# Beaglebone.net
KiCad netlist of a schematic drawn in Altium Designer
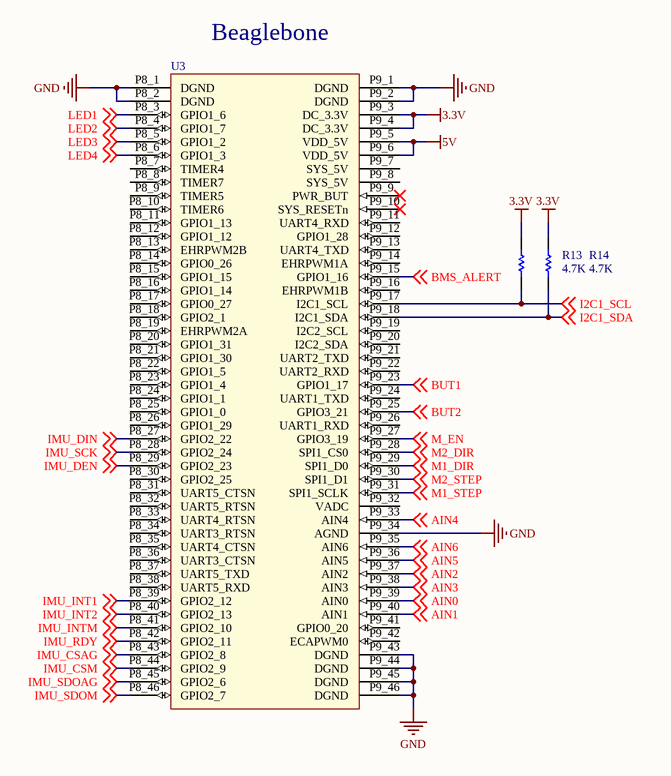
[diagram p0: Beaglebone.SchDoc]

(export (version "E")
  (design (tool "Eeschema 10.0.6"))
  (components
    (comp (ref "R13")
      (value "4.7K")
      (footprint "J1-0603")
      (description "RES SMD 4.7K OHM 5% 1/10W 0603")
      (libsource (lib "Miscellaneous Devices") (part "Res1"))
    )
    (comp (ref "R14")
      (value "4.7K")
      (footprint "J1-0603")
      (description "RES SMD 4.7K OHM 5% 1/10W 0603")
      (libsource (lib "Miscellaneous Devices") (part "Res1"))
    )
    (comp (ref "U3")
      (value "Beaglebone Black")
      (footprint "BEAGLEBONE_BLACK")
      (libsource (lib "MicromouseLib") (part "Beaglebone Black"))
    )
  )
  (nets
    (net (code "1") (name "3.3V") (class "Default")
      (node (ref "R13") (pin "2") (pinfunction "2_2") (pintype "passive"))
      (node (ref "R14") (pin "2") (pinfunction "2_2") (pintype "passive"))
      (node (ref "U3") (pin "P9_3") (pinfunction "DC_3.3V_P9_3") (pintype "power_in"))
      (node (ref "U3") (pin "P9_4") (pinfunction "DC_3.3V_P9_4") (pintype "power_in"))
    )
    (net (code "2") (name "5V") (class "Default")
      (node (ref "U3") (pin "P9_5") (pinfunction "VDD_5V_P9_5") (pintype "power_in"))
      (node (ref "U3") (pin "P9_6") (pinfunction "VDD_5V_P9_6") (pintype "power_in"))
    )
    (net (code "3") (name "AIN0") (class "Default")
      (node (ref "U3") (pin "P9_39") (pinfunction "AIN0_P9_39") (pintype "input"))
    )
    (net (code "4") (name "AIN1") (class "Default")
      (node (ref "U3") (pin "P9_40") (pinfunction "AIN1_P9_40") (pintype "input"))
    )
    (net (code "5") (name "AIN2") (class "Default")
      (node (ref "U3") (pin "P9_37") (pinfunction "AIN2_P9_37") (pintype "input"))
    )
    (net (code "6") (name "AIN3") (class "Default")
      (node (ref "U3") (pin "P9_38") (pinfunction "AIN3_P9_38") (pintype "input"))
    )
    (net (code "7") (name "AIN4") (class "Default")
      (node (ref "U3") (pin "P9_33") (pinfunction "AIN4_P9_33") (pintype "input"))
    )
    (net (code "8") (name "AIN5") (class "Default")
      (node (ref "U3") (pin "P9_36") (pinfunction "AIN5_P9_36") (pintype "input"))
    )
    (net (code "9") (name "AIN6") (class "Default")
      (node (ref "U3") (pin "P9_35") (pinfunction "AIN6_P9_35") (pintype "input"))
    )
    (net (code "10") (name "BMS_ALERT") (class "Default")
      (node (ref "U3") (pin "P9_15") (pinfunction "GPIO1_16_P9_15") (pintype "bidirectional"))
    )
    (net (code "11") (name "BUT1") (class "Default")
      (node (ref "U3") (pin "P9_23") (pinfunction "GPIO1_17_P9_23") (pintype "bidirectional"))
    )
    (net (code "12") (name "BUT2") (class "Default")
      (node (ref "U3") (pin "P9_25") (pinfunction "GPIO3_21_P9_25") (pintype "bidirectional"))
    )
    (net (code "13") (name "GND") (class "Default")
      (node (ref "U3") (pin "P8_1") (pinfunction "DGND_P8_1") (pintype "power_in"))
      (node (ref "U3") (pin "P8_2") (pinfunction "DGND_P8_2") (pintype "power_in"))
      (node (ref "U3") (pin "P9_1") (pinfunction "DGND_P9_1") (pintype "power_in"))
      (node (ref "U3") (pin "P9_2") (pinfunction "DGND_P9_2") (pintype "power_in"))
      (node (ref "U3") (pin "P9_34") (pinfunction "AGND_P9_34") (pintype "power_in"))
      (node (ref "U3") (pin "P9_43") (pinfunction "DGND_P9_43") (pintype "power_in"))
      (node (ref "U3") (pin "P9_44") (pinfunction "DGND_P9_44") (pintype "power_in"))
      (node (ref "U3") (pin "P9_45") (pinfunction "DGND_P9_45") (pintype "power_in"))
      (node (ref "U3") (pin "P9_46") (pinfunction "DGND_P9_46") (pintype "power_in"))
    )
    (net (code "14") (name "I2C1_SCL") (class "Default")
      (node (ref "R13") (pin "1") (pinfunction "1_1") (pintype "passive"))
      (node (ref "U3") (pin "P9_17") (pinfunction "I2C1_SCL_P9_17") (pintype "bidirectional"))
    )
    (net (code "15") (name "I2C1_SDA") (class "Default")
      (node (ref "R14") (pin "1") (pinfunction "1_1") (pintype "passive"))
      (node (ref "U3") (pin "P9_18") (pinfunction "I2C1_SDA_P9_18") (pintype "bidirectional"))
    )
    (net (code "16") (name "IMU_CSAG") (class "Default")
      (node (ref "U3") (pin "P8_43") (pinfunction "GPIO2_8_P8_43") (pintype "bidirectional"))
    )
    (net (code "17") (name "IMU_CSM") (class "Default")
      (node (ref "U3") (pin "P8_44") (pinfunction "GPIO2_9_P8_44") (pintype "bidirectional"))
    )
    (net (code "18") (name "IMU_DEN") (class "Default")
      (node (ref "U3") (pin "P8_29") (pinfunction "GPIO2_23_P8_29") (pintype "bidirectional"))
    )
    (net (code "19") (name "IMU_DIN") (class "Default")
      (node (ref "U3") (pin "P8_27") (pinfunction "GPIO2_22_P8_27") (pintype "bidirectional"))
    )
    (net (code "20") (name "IMU_INT1") (class "Default")
      (node (ref "U3") (pin "P8_39") (pinfunction "GPIO2_12_P8_39") (pintype "bidirectional"))
    )
    (net (code "21") (name "IMU_INT2") (class "Default")
      (node (ref "U3") (pin "P8_40") (pinfunction "GPIO2_13_P8_40") (pintype "bidirectional"))
    )
    (net (code "22") (name "IMU_INTM") (class "Default")
      (node (ref "U3") (pin "P8_41") (pinfunction "GPIO2_10_P8_41") (pintype "bidirectional"))
    )
    (net (code "23") (name "IMU_RDY") (class "Default")
      (node (ref "U3") (pin "P8_42") (pinfunction "GPIO2_11_P8_42") (pintype "bidirectional"))
    )
    (net (code "24") (name "IMU_SCK") (class "Default")
      (node (ref "U3") (pin "P8_28") (pinfunction "GPIO2_24_P8_28") (pintype "bidirectional"))
    )
    (net (code "25") (name "IMU_SDOAG") (class "Default")
      (node (ref "U3") (pin "P8_45") (pinfunction "GPIO2_6_P8_45") (pintype "bidirectional"))
    )
    (net (code "26") (name "IMU_SDOM") (class "Default")
      (node (ref "U3") (pin "P8_46") (pinfunction "GPIO2_7_P8_46") (pintype "bidirectional"))
    )
    (net (code "27") (name "LED1") (class "Default")
      (node (ref "U3") (pin "P8_3") (pinfunction "GPIO1_6_P8_3") (pintype "bidirectional"))
    )
    (net (code "28") (name "LED2") (class "Default")
      (node (ref "U3") (pin "P8_4") (pinfunction "GPIO1_7_P8_4") (pintype "bidirectional"))
    )
    (net (code "29") (name "LED3") (class "Default")
      (node (ref "U3") (pin "P8_5") (pinfunction "GPIO1_2_P8_5") (pintype "bidirectional"))
    )
    (net (code "30") (name "LED4") (class "Default")
      (node (ref "U3") (pin "P8_6") (pinfunction "GPIO1_3_P8_6") (pintype "bidirectional"))
    )
    (net (code "31") (name "M1_DIR") (class "Default")
      (node (ref "U3") (pin "P9_29") (pinfunction "SPI1_D0_P9_29") (pintype "bidirectional"))
    )
    (net (code "32") (name "M1_STEP") (class "Default")
      (node (ref "U3") (pin "P9_31") (pinfunction "SPI1_SCLK_P9_31") (pintype "bidirectional"))
    )
    (net (code "33") (name "M2_DIR") (class "Default")
      (node (ref "U3") (pin "P9_28") (pinfunction "SPI1_CS0_P9_28") (pintype "bidirectional"))
    )
    (net (code "34") (name "M2_STEP") (class "Default")
      (node (ref "U3") (pin "P9_30") (pinfunction "SPI1_D1_P9_30") (pintype "bidirectional"))
    )
    (net (code "35") (name "M_EN") (class "Default")
      (node (ref "U3") (pin "P9_27") (pinfunction "GPIO3_19_P9_27") (pintype "bidirectional"))
    )
    (net (code "36") (name "unconnected-(U3-ECAPWM0-PadP9_42)") (class "Default")
      (node (ref "U3") (pin "P9_42") (pinfunction "ECAPWM0_P9_42") (pintype "bidirectional"))
    )
    (net (code "37") (name "unconnected-(U3-EHRPWM1A-PadP9_14)") (class "Default")
      (node (ref "U3") (pin "P9_14") (pinfunction "EHRPWM1A_P9_14") (pintype "bidirectional"))
    )
    (net (code "38") (name "unconnected-(U3-EHRPWM1B-PadP9_16)") (class "Default")
      (node (ref "U3") (pin "P9_16") (pinfunction "EHRPWM1B_P9_16") (pintype "bidirectional"))
    )
    (net (code "39") (name "unconnected-(U3-EHRPWM2A-PadP8_19)") (class "Default")
      (node (ref "U3") (pin "P8_19") (pinfunction "EHRPWM2A_P8_19") (pintype "bidirectional"))
    )
    (net (code "40") (name "unconnected-(U3-EHRPWM2B-PadP8_13)") (class "Default")
      (node (ref "U3") (pin "P8_13") (pinfunction "EHRPWM2B_P8_13") (pintype "bidirectional"))
    )
    (net (code "41") (name "unconnected-(U3-GPIO0_20-PadP9_41)") (class "Default")
      (node (ref "U3") (pin "P9_41") (pinfunction "GPIO0_20_P9_41") (pintype "bidirectional"))
    )
    (net (code "42") (name "unconnected-(U3-GPIO0_26-PadP8_14)") (class "Default")
      (node (ref "U3") (pin "P8_14") (pinfunction "GPIO0_26_P8_14") (pintype "bidirectional"))
    )
    (net (code "43") (name "unconnected-(U3-GPIO0_27-PadP8_17)") (class "Default")
      (node (ref "U3") (pin "P8_17") (pinfunction "GPIO0_27_P8_17") (pintype "bidirectional"))
    )
    (net (code "44") (name "unconnected-(U3-GPIO1_0-PadP8_25)") (class "Default")
      (node (ref "U3") (pin "P8_25") (pinfunction "GPIO1_0_P8_25") (pintype "bidirectional"))
    )
    (net (code "45") (name "unconnected-(U3-GPIO1_1-PadP8_24)") (class "Default")
      (node (ref "U3") (pin "P8_24") (pinfunction "GPIO1_1_P8_24") (pintype "bidirectional"))
    )
    (net (code "46") (name "unconnected-(U3-GPIO1_4-PadP8_23)") (class "Default")
      (node (ref "U3") (pin "P8_23") (pinfunction "GPIO1_4_P8_23") (pintype "bidirectional"))
    )
    (net (code "47") (name "unconnected-(U3-GPIO1_5-PadP8_22)") (class "Default")
      (node (ref "U3") (pin "P8_22") (pinfunction "GPIO1_5_P8_22") (pintype "bidirectional"))
    )
    (net (code "48") (name "unconnected-(U3-GPIO1_12-PadP8_12)") (class "Default")
      (node (ref "U3") (pin "P8_12") (pinfunction "GPIO1_12_P8_12") (pintype "bidirectional"))
    )
    (net (code "49") (name "unconnected-(U3-GPIO1_13-PadP8_11)") (class "Default")
      (node (ref "U3") (pin "P8_11") (pinfunction "GPIO1_13_P8_11") (pintype "bidirectional"))
    )
    (net (code "50") (name "unconnected-(U3-GPIO1_14-PadP8_16)") (class "Default")
      (node (ref "U3") (pin "P8_16") (pinfunction "GPIO1_14_P8_16") (pintype "bidirectional"))
    )
    (net (code "51") (name "unconnected-(U3-GPIO1_15-PadP8_15)") (class "Default")
      (node (ref "U3") (pin "P8_15") (pinfunction "GPIO1_15_P8_15") (pintype "bidirectional"))
    )
    (net (code "52") (name "unconnected-(U3-GPIO1_28-PadP9_12)") (class "Default")
      (node (ref "U3") (pin "P9_12") (pinfunction "GPIO1_28_P9_12") (pintype "bidirectional"))
    )
    (net (code "53") (name "unconnected-(U3-GPIO1_29-PadP8_26)") (class "Default")
      (node (ref "U3") (pin "P8_26") (pinfunction "GPIO1_29_P8_26") (pintype "bidirectional"))
    )
    (net (code "54") (name "unconnected-(U3-GPIO1_30-PadP8_21)") (class "Default")
      (node (ref "U3") (pin "P8_21") (pinfunction "GPIO1_30_P8_21") (pintype "bidirectional"))
    )
    (net (code "55") (name "unconnected-(U3-GPIO1_31-PadP8_20)") (class "Default")
      (node (ref "U3") (pin "P8_20") (pinfunction "GPIO1_31_P8_20") (pintype "bidirectional"))
    )
    (net (code "56") (name "unconnected-(U3-GPIO2_1-PadP8_18)") (class "Default")
      (node (ref "U3") (pin "P8_18") (pinfunction "GPIO2_1_P8_18") (pintype "bidirectional"))
    )
    (net (code "57") (name "unconnected-(U3-GPIO2_25-PadP8_30)") (class "Default")
      (node (ref "U3") (pin "P8_30") (pinfunction "GPIO2_25_P8_30") (pintype "bidirectional"))
    )
    (net (code "58") (name "unconnected-(U3-I2C2_SCL-PadP9_19)") (class "Default")
      (node (ref "U3") (pin "P9_19") (pinfunction "I2C2_SCL_P9_19") (pintype "bidirectional"))
    )
    (net (code "59") (name "unconnected-(U3-I2C2_SDA-PadP9_20)") (class "Default")
      (node (ref "U3") (pin "P9_20") (pinfunction "I2C2_SDA_P9_20") (pintype "bidirectional"))
    )
    (net (code "60") (name "unconnected-(U3-PWR_BUT-PadP9_9)") (class "Default")
      (node (ref "U3") (pin "P9_9") (pinfunction "PWR_BUT_P9_9") (pintype "input+no_connect"))
    )
    (net (code "61") (name "unconnected-(U3-SYS_5V-PadP9_7)") (class "Default")
      (node (ref "U3") (pin "P9_7") (pinfunction "SYS_5V_P9_7") (pintype "power_in"))
    )
    (net (code "62") (name "unconnected-(U3-SYS_5V-PadP9_8)") (class "Default")
      (node (ref "U3") (pin "P9_8") (pinfunction "SYS_5V_P9_8") (pintype "power_in"))
    )
    (net (code "63") (name "unconnected-(U3-SYS_RESETn-PadP9_10)") (class "Default")
      (node (ref "U3") (pin "P9_10") (pinfunction "SYS_RESETn_P9_10") (pintype "input+no_connect"))
    )
    (net (code "64") (name "unconnected-(U3-TIMER4-PadP8_7)") (class "Default")
      (node (ref "U3") (pin "P8_7") (pinfunction "TIMER4_P8_7") (pintype "bidirectional"))
    )
    (net (code "65") (name "unconnected-(U3-TIMER5-PadP8_9)") (class "Default")
      (node (ref "U3") (pin "P8_9") (pinfunction "TIMER5_P8_9") (pintype "bidirectional"))
    )
    (net (code "66") (name "unconnected-(U3-TIMER6-PadP8_10)") (class "Default")
      (node (ref "U3") (pin "P8_10") (pinfunction "TIMER6_P8_10") (pintype "bidirectional"))
    )
    (net (code "67") (name "unconnected-(U3-TIMER7-PadP8_8)") (class "Default")
      (node (ref "U3") (pin "P8_8") (pinfunction "TIMER7_P8_8") (pintype "bidirectional"))
    )
    (net (code "68") (name "unconnected-(U3-UART1_RXD-PadP9_26)") (class "Default")
      (node (ref "U3") (pin "P9_26") (pinfunction "UART1_RXD_P9_26") (pintype "bidirectional"))
    )
    (net (code "69") (name "unconnected-(U3-UART1_TXD-PadP9_24)") (class "Default")
      (node (ref "U3") (pin "P9_24") (pinfunction "UART1_TXD_P9_24") (pintype "bidirectional"))
    )
    (net (code "70") (name "unconnected-(U3-UART2_RXD-PadP9_22)") (class "Default")
      (node (ref "U3") (pin "P9_22") (pinfunction "UART2_RXD_P9_22") (pintype "bidirectional"))
    )
    (net (code "71") (name "unconnected-(U3-UART2_TXD-PadP9_21)") (class "Default")
      (node (ref "U3") (pin "P9_21") (pinfunction "UART2_TXD_P9_21") (pintype "bidirectional"))
    )
    (net (code "72") (name "unconnected-(U3-UART3_CTSN-PadP8_36)") (class "Default")
      (node (ref "U3") (pin "P8_36") (pinfunction "UART3_CTSN_P8_36") (pintype "bidirectional"))
    )
    (net (code "73") (name "unconnected-(U3-UART3_RTSN-PadP8_34)") (class "Default")
      (node (ref "U3") (pin "P8_34") (pinfunction "UART3_RTSN_P8_34") (pintype "bidirectional"))
    )
    (net (code "74") (name "unconnected-(U3-UART4_CTSN-PadP8_35)") (class "Default")
      (node (ref "U3") (pin "P8_35") (pinfunction "UART4_CTSN_P8_35") (pintype "bidirectional"))
    )
    (net (code "75") (name "unconnected-(U3-UART4_RTSN-PadP8_33)") (class "Default")
      (node (ref "U3") (pin "P8_33") (pinfunction "UART4_RTSN_P8_33") (pintype "bidirectional"))
    )
    (net (code "76") (name "unconnected-(U3-UART4_RXD-PadP9_11)") (class "Default")
      (node (ref "U3") (pin "P9_11") (pinfunction "UART4_RXD_P9_11") (pintype "bidirectional"))
    )
    (net (code "77") (name "unconnected-(U3-UART4_TXD-PadP9_13)") (class "Default")
      (node (ref "U3") (pin "P9_13") (pinfunction "UART4_TXD_P9_13") (pintype "bidirectional"))
    )
    (net (code "78") (name "unconnected-(U3-UART5_CTSN-PadP8_31)") (class "Default")
      (node (ref "U3") (pin "P8_31") (pinfunction "UART5_CTSN_P8_31") (pintype "bidirectional"))
    )
    (net (code "79") (name "unconnected-(U3-UART5_RTSN-PadP8_32)") (class "Default")
      (node (ref "U3") (pin "P8_32") (pinfunction "UART5_RTSN_P8_32") (pintype "bidirectional"))
    )
    (net (code "80") (name "unconnected-(U3-UART5_RXD-PadP8_38)") (class "Default")
      (node (ref "U3") (pin "P8_38") (pinfunction "UART5_RXD_P8_38") (pintype "bidirectional"))
    )
    (net (code "81") (name "unconnected-(U3-UART5_TXD-PadP8_37)") (class "Default")
      (node (ref "U3") (pin "P8_37") (pinfunction "UART5_TXD_P8_37") (pintype "bidirectional"))
    )
    (net (code "82") (name "unconnected-(U3-VADC-PadP9_32)") (class "Default")
      (node (ref "U3") (pin "P9_32") (pinfunction "VADC_P9_32") (pintype "power_in"))
    )
  )
)
